# Cartemoteur.net
KiCad netlist of a schematic drawn in EAGLE
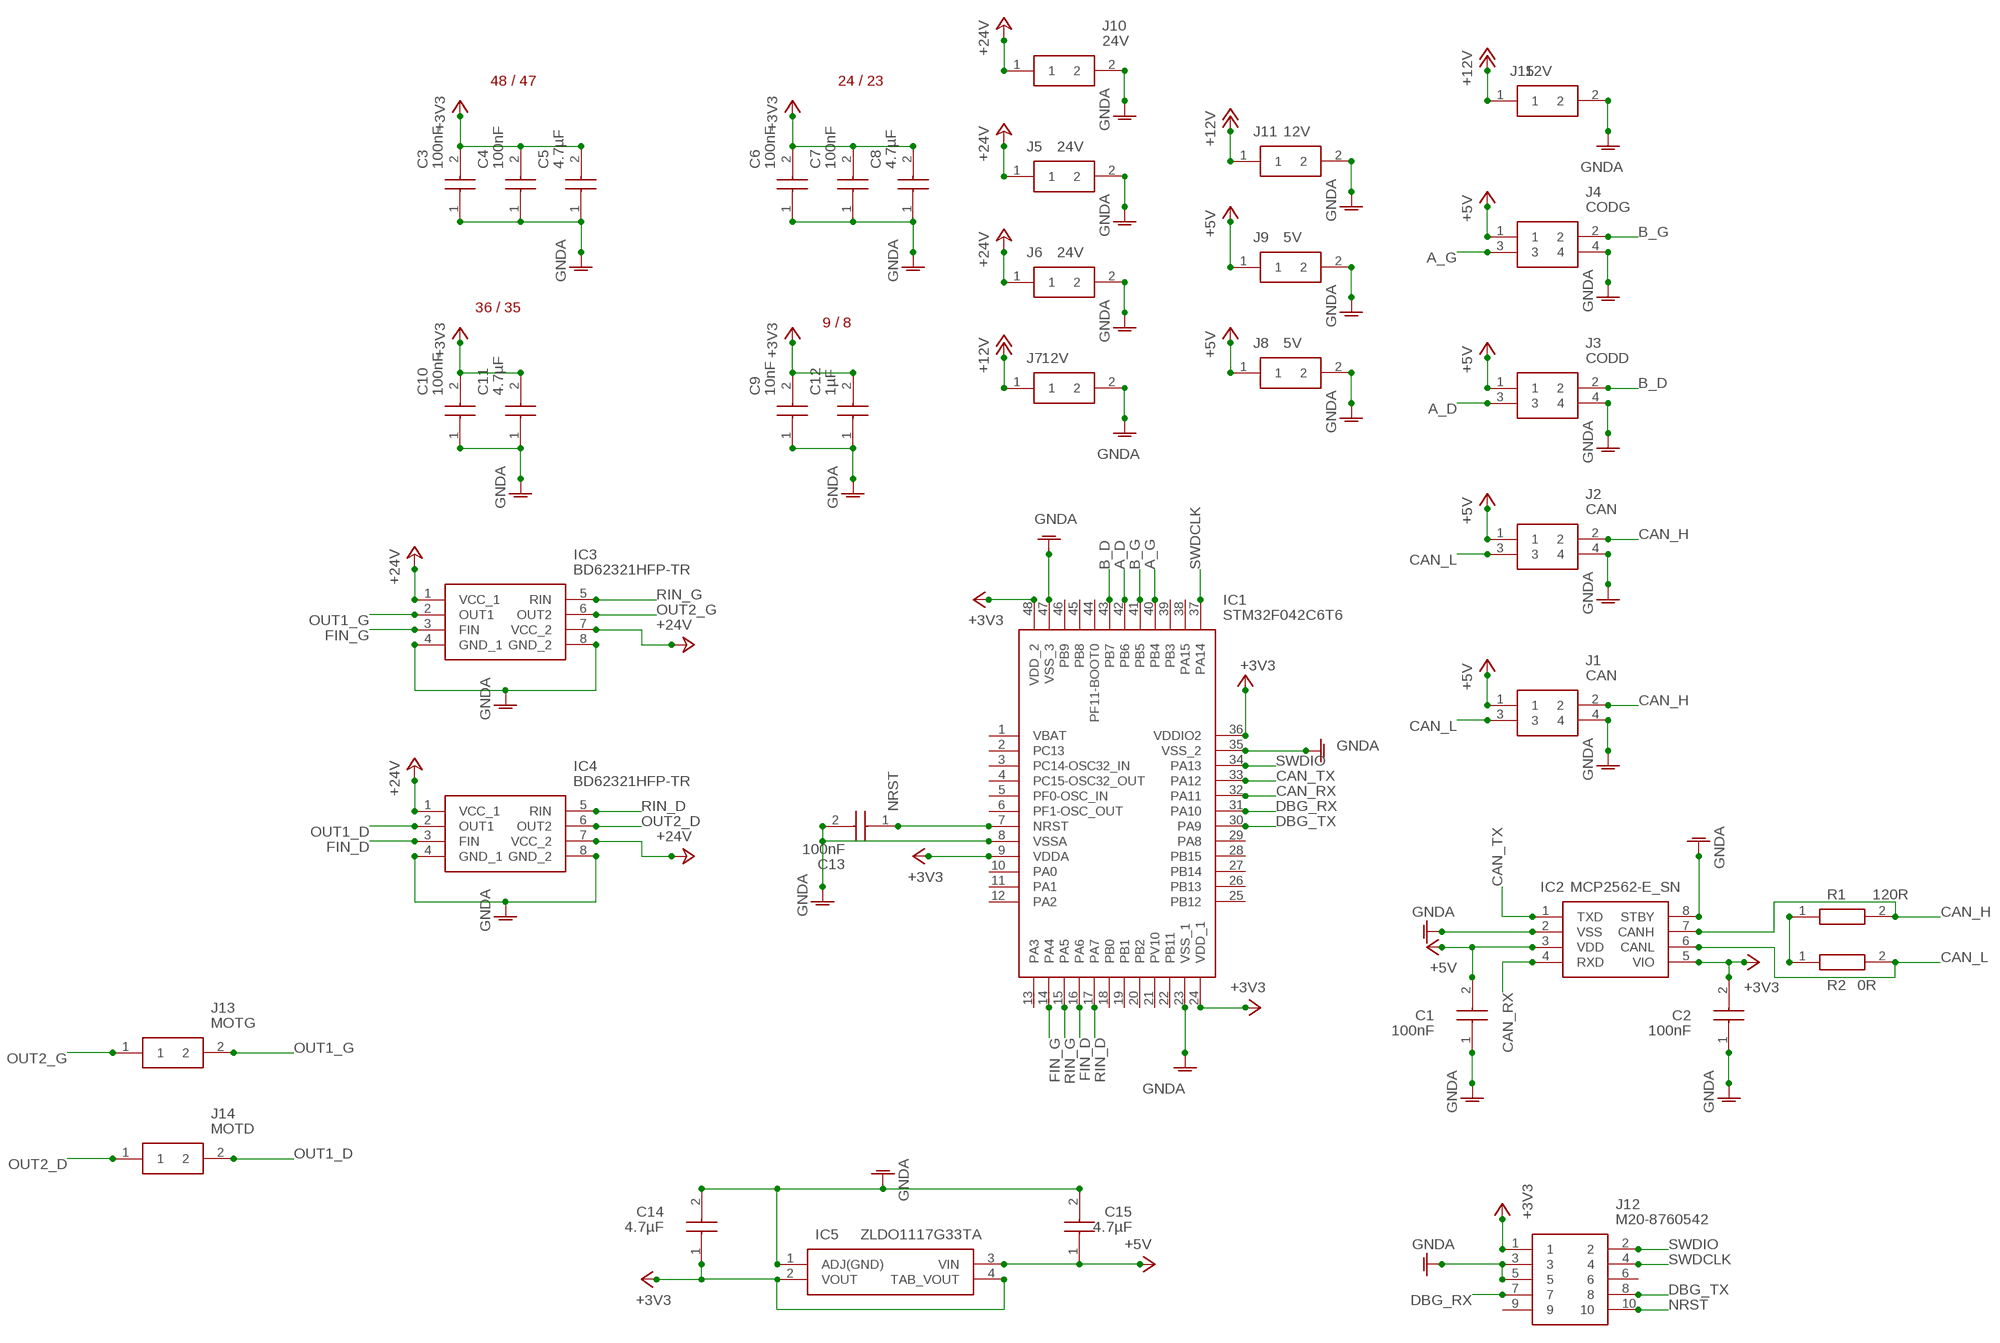
[diagram p0: schematic, sheet 1]

(export (version "E")
  (design (tool "Eeschema 10.0.6"))
  (components
    (comp (ref "C1")
      (value "100nF")
      (footprint "eagle-import:CAPC1608X90N")
      (fields
        (field (name "MANUFACTURER_PART_NUMBER") "06035C104K4T2A")
        (field (name "MOUSER_PART_NUMBER") "581-06035C104K4")
        (field (name "RS_PART_NUMBER") "6983251P")
      )
      (libsource (lib "eagle-import") (part "06035C104K4T2A"))
    )
    (comp (ref "C2")
      (value "100nF")
      (footprint "eagle-import:CAPC1608X90N")
      (fields
        (field (name "MANUFACTURER_PART_NUMBER") "06035C104K4T2A")
        (field (name "MOUSER_PART_NUMBER") "581-06035C104K4")
        (field (name "RS_PART_NUMBER") "6983251P")
      )
      (libsource (lib "eagle-import") (part "06035C104K4T2A"))
    )
    (comp (ref "C3")
      (value "100nF")
      (footprint "eagle-import:CAPC1608X90N")
      (fields
        (field (name "MANUFACTURER_PART_NUMBER") "06035C104K4T2A")
        (field (name "MOUSER_PART_NUMBER") "581-06035C104K4")
        (field (name "RS_PART_NUMBER") "6983251P")
      )
      (libsource (lib "eagle-import") (part "06035C104K4T2A"))
    )
    (comp (ref "C4")
      (value "100nF")
      (footprint "eagle-import:CAPC1608X90N")
      (fields
        (field (name "MANUFACTURER_PART_NUMBER") "06035C104K4T2A")
        (field (name "MOUSER_PART_NUMBER") "581-06035C104K4")
        (field (name "RS_PART_NUMBER") "6983251P")
      )
      (libsource (lib "eagle-import") (part "06035C104K4T2A"))
    )
    (comp (ref "C5")
      (value "4.7µF")
      (footprint "eagle-import:CAPC2012X145N")
      (fields
        (field (name "MANUFACTURER_PART_NUMBER") "GRM21BR61E475KA12L")
        (field (name "MOUSER_PART_NUMBER") "81-GRM21BR61E475KA12")
        (field (name "RS_PART_NUMBER") "7236057")
      )
      (libsource (lib "eagle-import") (part "GRM21BR61E475KA12L"))
    )
    (comp (ref "C6")
      (value "100nF")
      (footprint "eagle-import:CAPC1608X90N")
      (fields
        (field (name "MANUFACTURER_PART_NUMBER") "06035C104K4T2A")
        (field (name "MOUSER_PART_NUMBER") "581-06035C104K4")
        (field (name "RS_PART_NUMBER") "6983251P")
      )
      (libsource (lib "eagle-import") (part "06035C104K4T2A"))
    )
    (comp (ref "C7")
      (value "100nF")
      (footprint "eagle-import:CAPC1608X90N")
      (fields
        (field (name "MANUFACTURER_PART_NUMBER") "06035C104K4T2A")
        (field (name "MOUSER_PART_NUMBER") "581-06035C104K4")
        (field (name "RS_PART_NUMBER") "6983251P")
      )
      (libsource (lib "eagle-import") (part "06035C104K4T2A"))
    )
    (comp (ref "C8")
      (value "4.7µF")
      (footprint "eagle-import:CAPC2012X145N")
      (fields
        (field (name "MANUFACTURER_PART_NUMBER") "GRM21BR61E475KA12L")
        (field (name "MOUSER_PART_NUMBER") "81-GRM21BR61E475KA12")
        (field (name "RS_PART_NUMBER") "7236057")
      )
      (libsource (lib "eagle-import") (part "GRM21BR61E475KA12L"))
    )
    (comp (ref "C9")
      (value "10nF")
      (footprint "eagle-import:CAPC0603X33N")
      (fields
        (field (name "MANUFACTURER_PART_NUMBER") "GRM033R61E103KA12D")
        (field (name "MOUSER_PART_NUMBER") "81-GRM033R61E103KA2D")
        (field (name "RS_PART_NUMBER") "8200661")
      )
      (libsource (lib "eagle-import") (part "GRM033R61E103KA12D"))
    )
    (comp (ref "C10")
      (value "100nF")
      (footprint "eagle-import:CAPC1608X90N")
      (fields
        (field (name "MANUFACTURER_PART_NUMBER") "06035C104K4T2A")
        (field (name "MOUSER_PART_NUMBER") "581-06035C104K4")
        (field (name "RS_PART_NUMBER") "6983251P")
      )
      (libsource (lib "eagle-import") (part "06035C104K4T2A"))
    )
    (comp (ref "C11")
      (value "4.7µF")
      (footprint "eagle-import:CAPC2012X145N")
      (fields
        (field (name "MANUFACTURER_PART_NUMBER") "GRM21BR61E475KA12L")
        (field (name "MOUSER_PART_NUMBER") "81-GRM21BR61E475KA12")
        (field (name "RS_PART_NUMBER") "7236057")
      )
      (libsource (lib "eagle-import") (part "GRM21BR61E475KA12L"))
    )
    (comp (ref "C12")
      (value "1µF")
      (footprint "eagle-import:CAPC1005X55N")
      (fields
        (field (name "MANUFACTURER_PART_NUMBER") "GRM155B31E105KA12D")
        (field (name "RS_PART_NUMBER") "8847071P")
      )
      (libsource (lib "eagle-import") (part "GRM155B31E105KA12D"))
    )
    (comp (ref "C13")
      (value "100nF")
      (footprint "eagle-import:CAPC1608X90N")
      (fields
        (field (name "MANUFACTURER_PART_NUMBER") "06035C104K4T2A")
        (field (name "MOUSER_PART_NUMBER") "581-06035C104K4")
        (field (name "RS_PART_NUMBER") "6983251P")
      )
      (libsource (lib "eagle-import") (part "06035C104K4T2A"))
    )
    (comp (ref "C14")
      (value "4.7µF")
      (footprint "eagle-import:CAPC2012X145N")
      (fields
        (field (name "MANUFACTURER_PART_NUMBER") "GRM21BR61E475KA12L")
        (field (name "MOUSER_PART_NUMBER") "81-GRM21BR61E475KA12")
        (field (name "RS_PART_NUMBER") "7236057")
      )
      (libsource (lib "eagle-import") (part "GRM21BR61E475KA12L"))
    )
    (comp (ref "C15")
      (value "4.7µF")
      (footprint "eagle-import:CAPC2012X145N")
      (fields
        (field (name "MANUFACTURER_PART_NUMBER") "GRM21BR61E475KA12L")
        (field (name "MOUSER_PART_NUMBER") "81-GRM21BR61E475KA12")
        (field (name "RS_PART_NUMBER") "7236057")
      )
      (libsource (lib "eagle-import") (part "GRM21BR61E475KA12L"))
    )
    (comp (ref "IC1")
      (value "STM32F042C6T6")
      (footprint "eagle-import:QFP50P900X900X160-48N")
      (fields
        (field (name "MOUSER_PART_NUMBER") "511-STM32F042C6T6")
        (field (name "RS_PART_NUMBER") "1106612P")
      )
      (libsource (lib "eagle-import") (part "STM32F042C6T6"))
    )
    (comp (ref "IC2")
      (value "MCP2562-E_SN")
      (footprint "eagle-import:SOIC127P600X175-8N")
      (fields
        (field (name "MANUFACTURER_PART_NUMBER") "MCP2562-E/SN")
        (field (name "MOUSER_PART_NUMBER") "579-MCP2562-E/SN")
        (field (name "RS_PART_NUMBER") "7990228P")
      )
      (libsource (lib "eagle-import") (part "MCP2562-E_SN"))
    )
    (comp (ref "IC3")
      (value "BD62321HFP-TR")
      (footprint "eagle-import:HRP7")
      (fields
        (field (name "MOUSER_PART_NUMBER") "755-BD62321HFP-TR")
        (field (name "RS_PART_NUMBER") "1246483P")
      )
      (libsource (lib "eagle-import") (part "BD62321HFP-TR"))
    )
    (comp (ref "IC4")
      (value "BD62321HFP-TR")
      (footprint "eagle-import:HRP7")
      (fields
        (field (name "MOUSER_PART_NUMBER") "755-BD62321HFP-TR")
        (field (name "RS_PART_NUMBER") "1246483P")
      )
      (libsource (lib "eagle-import") (part "BD62321HFP-TR"))
    )
    (comp (ref "IC5")
      (value "ZLDO1117G33TA")
      (footprint "eagle-import:SOT230P700X180-4N")
      (fields
        (field (name "MOUSER_PART_NUMBER") "522-ZLDO1117G33TA")
        (field (name "RS_PART_NUMBER") "7515183P")
      )
      (libsource (lib "eagle-import") (part "ZLDO1117G33TA"))
    )
    (comp (ref "J1")
      (value "CAN")
      (footprint "eagle-import:436500400")
      (fields
        (field (name "MANUFACTURER_PART_NUMBER") "43650-0400")
        (field (name "MOUSER_PART_NUMBER") "538-43650-0400")
        (field (name "RS_PART_NUMBER") "6704733P")
      )
      (libsource (lib "eagle-import") (part "43650-0400"))
    )
    (comp (ref "J2")
      (value "CAN")
      (footprint "eagle-import:436500400")
      (fields
        (field (name "MANUFACTURER_PART_NUMBER") "43650-0400")
        (field (name "MOUSER_PART_NUMBER") "538-43650-0400")
        (field (name "RS_PART_NUMBER") "6704733P")
      )
      (libsource (lib "eagle-import") (part "43650-0400"))
    )
    (comp (ref "J3")
      (value "CODD")
      (footprint "eagle-import:436500400")
      (fields
        (field (name "MANUFACTURER_PART_NUMBER") "43650-0400")
        (field (name "MOUSER_PART_NUMBER") "538-43650-0400")
        (field (name "RS_PART_NUMBER") "6704733P")
      )
      (libsource (lib "eagle-import") (part "43650-0400"))
    )
    (comp (ref "J4")
      (value "CODG")
      (footprint "eagle-import:436500400")
      (fields
        (field (name "MANUFACTURER_PART_NUMBER") "43650-0400")
        (field (name "MOUSER_PART_NUMBER") "538-43650-0400")
        (field (name "RS_PART_NUMBER") "6704733P")
      )
      (libsource (lib "eagle-import") (part "43650-0400"))
    )
    (comp (ref "J5")
      (value "24V")
      (footprint "eagle-import:43650-0200")
      (fields
        (field (name "MANUFACTURER_PART_NUMBER") "43650-0200")
        (field (name "MOUSER_PART_NUMBER") "538-43650-0200")
        (field (name "RS_PART_NUMBER") "6704698P")
      )
      (libsource (lib "eagle-import") (part "43650-0200"))
    )
    (comp (ref "J6")
      (value "24V")
      (footprint "eagle-import:43650-0200")
      (fields
        (field (name "MANUFACTURER_PART_NUMBER") "43650-0200")
        (field (name "MOUSER_PART_NUMBER") "538-43650-0200")
        (field (name "RS_PART_NUMBER") "6704698P")
      )
      (libsource (lib "eagle-import") (part "43650-0200"))
    )
    (comp (ref "J7")
      (value "12V")
      (footprint "eagle-import:43650-0200")
      (fields
        (field (name "MANUFACTURER_PART_NUMBER") "43650-0200")
        (field (name "MOUSER_PART_NUMBER") "538-43650-0200")
        (field (name "RS_PART_NUMBER") "6704698P")
      )
      (libsource (lib "eagle-import") (part "43650-0200"))
    )
    (comp (ref "J8")
      (value "5V")
      (footprint "eagle-import:43650-0200")
      (fields
        (field (name "MANUFACTURER_PART_NUMBER") "43650-0200")
        (field (name "MOUSER_PART_NUMBER") "538-43650-0200")
        (field (name "RS_PART_NUMBER") "6704698P")
      )
      (libsource (lib "eagle-import") (part "43650-0200"))
    )
    (comp (ref "J9")
      (value "5V")
      (footprint "eagle-import:43650-0200")
      (fields
        (field (name "MANUFACTURER_PART_NUMBER") "43650-0200")
        (field (name "MOUSER_PART_NUMBER") "538-43650-0200")
        (field (name "RS_PART_NUMBER") "6704698P")
      )
      (libsource (lib "eagle-import") (part "43650-0200"))
    )
    (comp (ref "J10")
      (value "24V")
      (footprint "eagle-import:43650-0200")
      (fields
        (field (name "MANUFACTURER_PART_NUMBER") "43650-0200")
        (field (name "MOUSER_PART_NUMBER") "538-43650-0200")
        (field (name "RS_PART_NUMBER") "6704698P")
      )
      (libsource (lib "eagle-import") (part "43650-0200"))
    )
    (comp (ref "J11")
      (value "12V")
      (footprint "eagle-import:43650-0200")
      (fields
        (field (name "MANUFACTURER_PART_NUMBER") "43650-0200")
        (field (name "MOUSER_PART_NUMBER") "538-43650-0200")
        (field (name "RS_PART_NUMBER") "6704698P")
      )
      (libsource (lib "eagle-import") (part "43650-0200"))
    )
    (comp (ref "J12")
      (value "M20-8760542")
      (footprint "eagle-import:M208760542")
      (fields
        (field (name "MOUSER_PART_NUMBER") "855-M20-8760542")
        (field (name "RS_PART_NUMBER") "6812893P")
      )
      (libsource (lib "eagle-import") (part "M20-8760542"))
    )
    (comp (ref "J13")
      (value "MOTG")
      (footprint "eagle-import:43650-0200")
      (fields
        (field (name "MANUFACTURER_PART_NUMBER") "43650-0200")
        (field (name "MOUSER_PART_NUMBER") "538-43650-0200")
        (field (name "RS_PART_NUMBER") "6704698P")
      )
      (libsource (lib "eagle-import") (part "43650-0200"))
    )
    (comp (ref "J14")
      (value "MOTD")
      (footprint "eagle-import:43650-0200")
      (fields
        (field (name "MANUFACTURER_PART_NUMBER") "43650-0200")
        (field (name "MOUSER_PART_NUMBER") "538-43650-0200")
        (field (name "RS_PART_NUMBER") "6704698P")
      )
      (libsource (lib "eagle-import") (part "43650-0200"))
    )
    (comp (ref "J15")
      (value "12V")
      (footprint "eagle-import:43650-0200")
      (fields
        (field (name "MANUFACTURER_PART_NUMBER") "43650-0200")
        (field (name "MOUSER_PART_NUMBER") "538-43650-0200")
        (field (name "RS_PART_NUMBER") "6704698P")
      )
      (libsource (lib "eagle-import") (part "43650-0200"))
    )
    (comp (ref "R1")
      (value "120R")
      (footprint "eagle-import:RESC1608X50N")
      (fields
        (field (name "MANUFACTURER_PART_NUMBER") "CRCW0603120RFKEA")
        (field (name "MOUSER_PART_NUMBER") "71-CRCW0603-120-E3")
        (field (name "RS_PART_NUMBER") "6789718")
      )
      (libsource (lib "eagle-import") (part "CRCW0603120RFKEA"))
    )
    (comp (ref "R2")
      (value "0R")
      (footprint "eagle-import:RESC1608X55N")
      (fields (field (name "MANUFACTURER_PART_NUMBER") "RK73Z1JTTDB"))
      (libsource (lib "eagle-import") (part "RK73Z1JTTDB"))
    )
  )
  (nets
    (net (code "1") (name "+3V3") (class "Default")
      (node (ref "C10") (pin "2") (pinfunction "2_2") (pintype "bidirectional"))
      (node (ref "C11") (pin "2") (pinfunction "2_2") (pintype "bidirectional"))
      (node (ref "C12") (pin "2") (pinfunction "2_2") (pintype "bidirectional"))
      (node (ref "C14") (pin "1") (pinfunction "1_1") (pintype "bidirectional"))
      (node (ref "C2") (pin "2") (pinfunction "2_2") (pintype "bidirectional"))
      (node (ref "C3") (pin "2") (pinfunction "2_2") (pintype "bidirectional"))
      (node (ref "C4") (pin "2") (pinfunction "2_2") (pintype "bidirectional"))
      (node (ref "C5") (pin "2") (pinfunction "2_2") (pintype "bidirectional"))
      (node (ref "C6") (pin "2") (pinfunction "2_2") (pintype "bidirectional"))
      (node (ref "C7") (pin "2") (pinfunction "2_2") (pintype "bidirectional"))
      (node (ref "C8") (pin "2") (pinfunction "2_2") (pintype "bidirectional"))
      (node (ref "C9") (pin "2") (pinfunction "2_2") (pintype "bidirectional"))
      (node (ref "IC1") (pin "24") (pinfunction "VDD_1_24") (pintype "bidirectional"))
      (node (ref "IC1") (pin "36") (pinfunction "VDDIO2_36") (pintype "bidirectional"))
      (node (ref "IC1") (pin "48") (pinfunction "VDD_2_48") (pintype "bidirectional"))
      (node (ref "IC1") (pin "9") (pinfunction "VDDA_9") (pintype "bidirectional"))
      (node (ref "IC2") (pin "5") (pinfunction "VIO_5") (pintype "bidirectional"))
      (node (ref "IC5") (pin "2") (pinfunction "VOUT_2") (pintype "output"))
      (node (ref "IC5") (pin "4") (pinfunction "TAB_VOUT_4") (pintype "output"))
      (node (ref "J12") (pin "1") (pinfunction "1_1") (pintype "bidirectional"))
    )
    (net (code "2") (name "+5V") (class "Default")
      (node (ref "C1") (pin "2") (pinfunction "2_2") (pintype "bidirectional"))
      (node (ref "C15") (pin "1") (pinfunction "1_1") (pintype "bidirectional"))
      (node (ref "IC2") (pin "3") (pinfunction "VDD_3") (pintype "bidirectional"))
      (node (ref "IC5") (pin "3") (pinfunction "VIN_3") (pintype "input"))
      (node (ref "J1") (pin "1") (pinfunction "1_1") (pintype "bidirectional"))
      (node (ref "J2") (pin "1") (pinfunction "1_1") (pintype "bidirectional"))
      (node (ref "J3") (pin "1") (pinfunction "1_1") (pintype "bidirectional"))
      (node (ref "J4") (pin "1") (pinfunction "1_1") (pintype "bidirectional"))
      (node (ref "J8") (pin "1") (pinfunction "1_1") (pintype "bidirectional"))
      (node (ref "J9") (pin "1") (pinfunction "1_1") (pintype "bidirectional"))
    )
    (net (code "3") (name "+12V") (class "Default")
      (node (ref "J11") (pin "1") (pinfunction "1_1") (pintype "bidirectional"))
      (node (ref "J15") (pin "1") (pinfunction "1_1") (pintype "bidirectional"))
      (node (ref "J7") (pin "1") (pinfunction "1_1") (pintype "bidirectional"))
    )
    (net (code "4") (name "+24V") (class "Default")
      (node (ref "IC3") (pin "1") (pinfunction "VCC_1_1") (pintype "bidirectional"))
      (node (ref "IC3") (pin "7") (pinfunction "VCC_2_7") (pintype "bidirectional"))
      (node (ref "IC4") (pin "1") (pinfunction "VCC_1_1") (pintype "bidirectional"))
      (node (ref "IC4") (pin "7") (pinfunction "VCC_2_7") (pintype "bidirectional"))
      (node (ref "J10") (pin "1") (pinfunction "1_1") (pintype "bidirectional"))
      (node (ref "J5") (pin "1") (pinfunction "1_1") (pintype "bidirectional"))
      (node (ref "J6") (pin "1") (pinfunction "1_1") (pintype "bidirectional"))
    )
    (net (code "5") (name "/A_D") (class "Default")
      (node (ref "IC1") (pin "42") (pinfunction "PB6_42") (pintype "bidirectional"))
      (node (ref "J3") (pin "3") (pinfunction "3_3") (pintype "bidirectional"))
    )
    (net (code "6") (name "/A_G") (class "Default")
      (node (ref "IC1") (pin "40") (pinfunction "PB4_40") (pintype "bidirectional"))
      (node (ref "J4") (pin "3") (pinfunction "3_3") (pintype "bidirectional"))
    )
    (net (code "7") (name "/B_D") (class "Default")
      (node (ref "IC1") (pin "43") (pinfunction "PB7_43") (pintype "bidirectional"))
      (node (ref "J3") (pin "2") (pinfunction "2_2") (pintype "bidirectional"))
    )
    (net (code "8") (name "/B_G") (class "Default")
      (node (ref "IC1") (pin "41") (pinfunction "PB5_41") (pintype "bidirectional"))
      (node (ref "J4") (pin "2") (pinfunction "2_2") (pintype "bidirectional"))
    )
    (net (code "9") (name "/CAN_H") (class "Default")
      (node (ref "IC2") (pin "7") (pinfunction "CANH_7") (pintype "bidirectional"))
      (node (ref "J1") (pin "2") (pinfunction "2_2") (pintype "bidirectional"))
      (node (ref "J2") (pin "2") (pinfunction "2_2") (pintype "bidirectional"))
      (node (ref "R1") (pin "2") (pinfunction "2_2") (pintype "bidirectional"))
    )
    (net (code "10") (name "/CAN_L") (class "Default")
      (node (ref "IC2") (pin "6") (pinfunction "CANL_6") (pintype "bidirectional"))
      (node (ref "J1") (pin "3") (pinfunction "3_3") (pintype "bidirectional"))
      (node (ref "J2") (pin "3") (pinfunction "3_3") (pintype "bidirectional"))
      (node (ref "R2") (pin "2") (pinfunction "2_2") (pintype "bidirectional"))
    )
    (net (code "11") (name "/CAN_RX") (class "Default")
      (node (ref "IC1") (pin "32") (pinfunction "PA11_32") (pintype "bidirectional"))
      (node (ref "IC2") (pin "4") (pinfunction "RXD_4") (pintype "bidirectional"))
    )
    (net (code "12") (name "/CAN_TX") (class "Default")
      (node (ref "IC1") (pin "33") (pinfunction "PA12_33") (pintype "bidirectional"))
      (node (ref "IC2") (pin "1") (pinfunction "TXD_1") (pintype "bidirectional"))
    )
    (net (code "13") (name "/DBG_RX") (class "Default")
      (node (ref "IC1") (pin "31") (pinfunction "PA10_31") (pintype "bidirectional"))
      (node (ref "J12") (pin "7") (pinfunction "7_7") (pintype "bidirectional"))
    )
    (net (code "14") (name "/DBG_TX") (class "Default")
      (node (ref "IC1") (pin "30") (pinfunction "PA9_30") (pintype "bidirectional"))
      (node (ref "J12") (pin "8") (pinfunction "8_8") (pintype "bidirectional"))
    )
    (net (code "15") (name "/FIN_D") (class "Default")
      (node (ref "IC1") (pin "16") (pinfunction "PA6_16") (pintype "bidirectional"))
      (node (ref "IC4") (pin "3") (pinfunction "FIN_3") (pintype "bidirectional"))
    )
    (net (code "16") (name "/FIN_G") (class "Default")
      (node (ref "IC1") (pin "14") (pinfunction "PA4_14") (pintype "bidirectional"))
      (node (ref "IC3") (pin "3") (pinfunction "FIN_3") (pintype "bidirectional"))
    )
    (net (code "17") (name "/NRST") (class "Default")
      (node (ref "C13") (pin "1") (pinfunction "1_1") (pintype "bidirectional"))
      (node (ref "IC1") (pin "7") (pinfunction "NRST_7") (pintype "bidirectional"))
      (node (ref "J12") (pin "10") (pinfunction "10_10") (pintype "bidirectional"))
    )
    (net (code "18") (name "/OUT1_D") (class "Default")
      (node (ref "IC4") (pin "2") (pinfunction "OUT1_2") (pintype "bidirectional"))
      (node (ref "J14") (pin "2") (pinfunction "2_2") (pintype "bidirectional"))
    )
    (net (code "19") (name "/OUT1_G") (class "Default")
      (node (ref "IC3") (pin "2") (pinfunction "OUT1_2") (pintype "bidirectional"))
      (node (ref "J13") (pin "2") (pinfunction "2_2") (pintype "bidirectional"))
    )
    (net (code "20") (name "/OUT2_D") (class "Default")
      (node (ref "IC4") (pin "6") (pinfunction "OUT2_6") (pintype "bidirectional"))
      (node (ref "J14") (pin "1") (pinfunction "1_1") (pintype "bidirectional"))
    )
    (net (code "21") (name "/OUT2_G") (class "Default")
      (node (ref "IC3") (pin "6") (pinfunction "OUT2_6") (pintype "bidirectional"))
      (node (ref "J13") (pin "1") (pinfunction "1_1") (pintype "bidirectional"))
    )
    (net (code "22") (name "/RIN_D") (class "Default")
      (node (ref "IC1") (pin "17") (pinfunction "PA7_17") (pintype "bidirectional"))
      (node (ref "IC4") (pin "5") (pinfunction "RIN_5") (pintype "bidirectional"))
    )
    (net (code "23") (name "/RIN_G") (class "Default")
      (node (ref "IC1") (pin "15") (pinfunction "PA5_15") (pintype "bidirectional"))
      (node (ref "IC3") (pin "5") (pinfunction "RIN_5") (pintype "bidirectional"))
    )
    (net (code "24") (name "/SWDCLK") (class "Default")
      (node (ref "IC1") (pin "37") (pinfunction "PA14_37") (pintype "bidirectional"))
      (node (ref "J12") (pin "4") (pinfunction "4_4") (pintype "bidirectional"))
    )
    (net (code "25") (name "/SWDIO") (class "Default")
      (node (ref "IC1") (pin "34") (pinfunction "PA13_34") (pintype "bidirectional"))
      (node (ref "J12") (pin "2") (pinfunction "2_2") (pintype "bidirectional"))
    )
    (net (code "26") (name "GNDA") (class "Default")
      (node (ref "C1") (pin "1") (pinfunction "1_1") (pintype "bidirectional"))
      (node (ref "C10") (pin "1") (pinfunction "1_1") (pintype "bidirectional"))
      (node (ref "C11") (pin "1") (pinfunction "1_1") (pintype "bidirectional"))
      (node (ref "C12") (pin "1") (pinfunction "1_1") (pintype "bidirectional"))
      (node (ref "C13") (pin "2") (pinfunction "2_2") (pintype "bidirectional"))
      (node (ref "C14") (pin "2") (pinfunction "2_2") (pintype "bidirectional"))
      (node (ref "C15") (pin "2") (pinfunction "2_2") (pintype "bidirectional"))
      (node (ref "C2") (pin "1") (pinfunction "1_1") (pintype "bidirectional"))
      (node (ref "C3") (pin "1") (pinfunction "1_1") (pintype "bidirectional"))
      (node (ref "C4") (pin "1") (pinfunction "1_1") (pintype "bidirectional"))
      (node (ref "C5") (pin "1") (pinfunction "1_1") (pintype "bidirectional"))
      (node (ref "C6") (pin "1") (pinfunction "1_1") (pintype "bidirectional"))
      (node (ref "C7") (pin "1") (pinfunction "1_1") (pintype "bidirectional"))
      (node (ref "C8") (pin "1") (pinfunction "1_1") (pintype "bidirectional"))
      (node (ref "C9") (pin "1") (pinfunction "1_1") (pintype "bidirectional"))
      (node (ref "IC1") (pin "23") (pinfunction "VSS_1_23") (pintype "bidirectional"))
      (node (ref "IC1") (pin "35") (pinfunction "VSS_2_35") (pintype "bidirectional"))
      (node (ref "IC1") (pin "47") (pinfunction "VSS_3_47") (pintype "bidirectional"))
      (node (ref "IC1") (pin "8") (pinfunction "VSSA_8") (pintype "bidirectional"))
      (node (ref "IC2") (pin "2") (pinfunction "VSS_2") (pintype "bidirectional"))
      (node (ref "IC2") (pin "8") (pinfunction "STBY_8") (pintype "bidirectional"))
      (node (ref "IC3") (pin "4") (pinfunction "GND_1_4") (pintype "bidirectional"))
      (node (ref "IC3") (pin "8") (pinfunction "GND_2_8") (pintype "bidirectional"))
      (node (ref "IC4") (pin "4") (pinfunction "GND_1_4") (pintype "bidirectional"))
      (node (ref "IC4") (pin "8") (pinfunction "GND_2_8") (pintype "bidirectional"))
      (node (ref "IC5") (pin "1") (pinfunction "ADJ(GND)_1") (pintype "power_in"))
      (node (ref "J1") (pin "4") (pinfunction "4_4") (pintype "bidirectional"))
      (node (ref "J10") (pin "2") (pinfunction "2_2") (pintype "bidirectional"))
      (node (ref "J11") (pin "2") (pinfunction "2_2") (pintype "bidirectional"))
      (node (ref "J12") (pin "3") (pinfunction "3_3") (pintype "bidirectional"))
      (node (ref "J12") (pin "5") (pinfunction "5_5") (pintype "bidirectional"))
      (node (ref "J15") (pin "2") (pinfunction "2_2") (pintype "bidirectional"))
      (node (ref "J2") (pin "4") (pinfunction "4_4") (pintype "bidirectional"))
      (node (ref "J3") (pin "4") (pinfunction "4_4") (pintype "bidirectional"))
      (node (ref "J4") (pin "4") (pinfunction "4_4") (pintype "bidirectional"))
      (node (ref "J5") (pin "2") (pinfunction "2_2") (pintype "bidirectional"))
      (node (ref "J6") (pin "2") (pinfunction "2_2") (pintype "bidirectional"))
      (node (ref "J7") (pin "2") (pinfunction "2_2") (pintype "bidirectional"))
      (node (ref "J8") (pin "2") (pinfunction "2_2") (pintype "bidirectional"))
      (node (ref "J9") (pin "2") (pinfunction "2_2") (pintype "bidirectional"))
    )
    (net (code "27") (name "Net-(R1-Pad1)") (class "Default")
      (node (ref "R1") (pin "1") (pinfunction "1_1") (pintype "bidirectional"))
      (node (ref "R2") (pin "1") (pinfunction "1_1") (pintype "bidirectional"))
    )
    (net (code "28") (name "unconnected-(IC1-PA0-Pad10)") (class "Default")
      (node (ref "IC1") (pin "10") (pinfunction "PA0_10") (pintype "bidirectional"))
    )
    (net (code "29") (name "unconnected-(IC1-PA1-Pad11)") (class "Default")
      (node (ref "IC1") (pin "11") (pinfunction "PA1_11") (pintype "bidirectional"))
    )
    (net (code "30") (name "unconnected-(IC1-PA2-Pad12)") (class "Default")
      (node (ref "IC1") (pin "12") (pinfunction "PA2_12") (pintype "bidirectional"))
    )
    (net (code "31") (name "unconnected-(IC1-PA3-Pad13)") (class "Default")
      (node (ref "IC1") (pin "13") (pinfunction "PA3_13") (pintype "bidirectional"))
    )
    (net (code "32") (name "unconnected-(IC1-PA8-Pad29)") (class "Default")
      (node (ref "IC1") (pin "29") (pinfunction "PA8_29") (pintype "bidirectional"))
    )
    (net (code "33") (name "unconnected-(IC1-PA15-Pad38)") (class "Default")
      (node (ref "IC1") (pin "38") (pinfunction "PA15_38") (pintype "bidirectional"))
    )
    (net (code "34") (name "unconnected-(IC1-PB0-Pad18)") (class "Default")
      (node (ref "IC1") (pin "18") (pinfunction "PB0_18") (pintype "bidirectional"))
    )
    (net (code "35") (name "unconnected-(IC1-PB1-Pad19)") (class "Default")
      (node (ref "IC1") (pin "19") (pinfunction "PB1_19") (pintype "bidirectional"))
    )
    (net (code "36") (name "unconnected-(IC1-PB2-Pad20)") (class "Default")
      (node (ref "IC1") (pin "20") (pinfunction "PB2_20") (pintype "bidirectional"))
    )
    (net (code "37") (name "unconnected-(IC1-PB3-Pad39)") (class "Default")
      (node (ref "IC1") (pin "39") (pinfunction "PB3_39") (pintype "bidirectional"))
    )
    (net (code "38") (name "unconnected-(IC1-PB8-Pad45)") (class "Default")
      (node (ref "IC1") (pin "45") (pinfunction "PB8_45") (pintype "bidirectional"))
    )
    (net (code "39") (name "unconnected-(IC1-PB9-Pad46)") (class "Default")
      (node (ref "IC1") (pin "46") (pinfunction "PB9_46") (pintype "bidirectional"))
    )
    (net (code "40") (name "unconnected-(IC1-PB11-Pad22)") (class "Default")
      (node (ref "IC1") (pin "22") (pinfunction "PB11_22") (pintype "bidirectional"))
    )
    (net (code "41") (name "unconnected-(IC1-PB12-Pad25)") (class "Default")
      (node (ref "IC1") (pin "25") (pinfunction "PB12_25") (pintype "bidirectional"))
    )
    (net (code "42") (name "unconnected-(IC1-PB13-Pad26)") (class "Default")
      (node (ref "IC1") (pin "26") (pinfunction "PB13_26") (pintype "bidirectional"))
    )
    (net (code "43") (name "unconnected-(IC1-PB14-Pad27)") (class "Default")
      (node (ref "IC1") (pin "27") (pinfunction "PB14_27") (pintype "bidirectional"))
    )
    (net (code "44") (name "unconnected-(IC1-PB15-Pad28)") (class "Default")
      (node (ref "IC1") (pin "28") (pinfunction "PB15_28") (pintype "bidirectional"))
    )
    (net (code "45") (name "unconnected-(IC1-PC13-Pad2)") (class "Default")
      (node (ref "IC1") (pin "2") (pinfunction "PC13_2") (pintype "bidirectional"))
    )
    (net (code "46") (name "unconnected-(IC1-PC14-OSC32_IN-Pad3)") (class "Default")
      (node (ref "IC1") (pin "3") (pinfunction "PC14-OSC32_IN_3") (pintype "bidirectional"))
    )
    (net (code "47") (name "unconnected-(IC1-PC15-OSC32_OUT-Pad4)") (class "Default")
      (node (ref "IC1") (pin "4") (pinfunction "PC15-OSC32_OUT_4") (pintype "bidirectional"))
    )
    (net (code "48") (name "unconnected-(IC1-PF0-OSC_IN-Pad5)") (class "Default")
      (node (ref "IC1") (pin "5") (pinfunction "PF0-OSC_IN_5") (pintype "bidirectional"))
    )
    (net (code "49") (name "unconnected-(IC1-PF1-OSC_OUT-Pad6)") (class "Default")
      (node (ref "IC1") (pin "6") (pinfunction "PF1-OSC_OUT_6") (pintype "bidirectional"))
    )
    (net (code "50") (name "unconnected-(IC1-PF11-BOOT0-Pad44)") (class "Default")
      (node (ref "IC1") (pin "44") (pinfunction "PF11-BOOT0_44") (pintype "bidirectional"))
    )
    (net (code "51") (name "unconnected-(IC1-PV10-Pad21)") (class "Default")
      (node (ref "IC1") (pin "21") (pinfunction "PV10_21") (pintype "bidirectional"))
    )
    (net (code "52") (name "unconnected-(IC1-VBAT-Pad1)") (class "Default")
      (node (ref "IC1") (pin "1") (pinfunction "VBAT_1") (pintype "bidirectional"))
    )
    (net (code "53") (name "unconnected-(J12-Pad6)") (class "Default")
      (node (ref "J12") (pin "6") (pinfunction "6_6") (pintype "bidirectional"))
    )
    (net (code "54") (name "unconnected-(J12-Pad9)") (class "Default")
      (node (ref "J12") (pin "9") (pinfunction "9_9") (pintype "bidirectional"))
    )
  )
)
